# Radio.net
KiCad netlist of a schematic drawn in Altium Designer
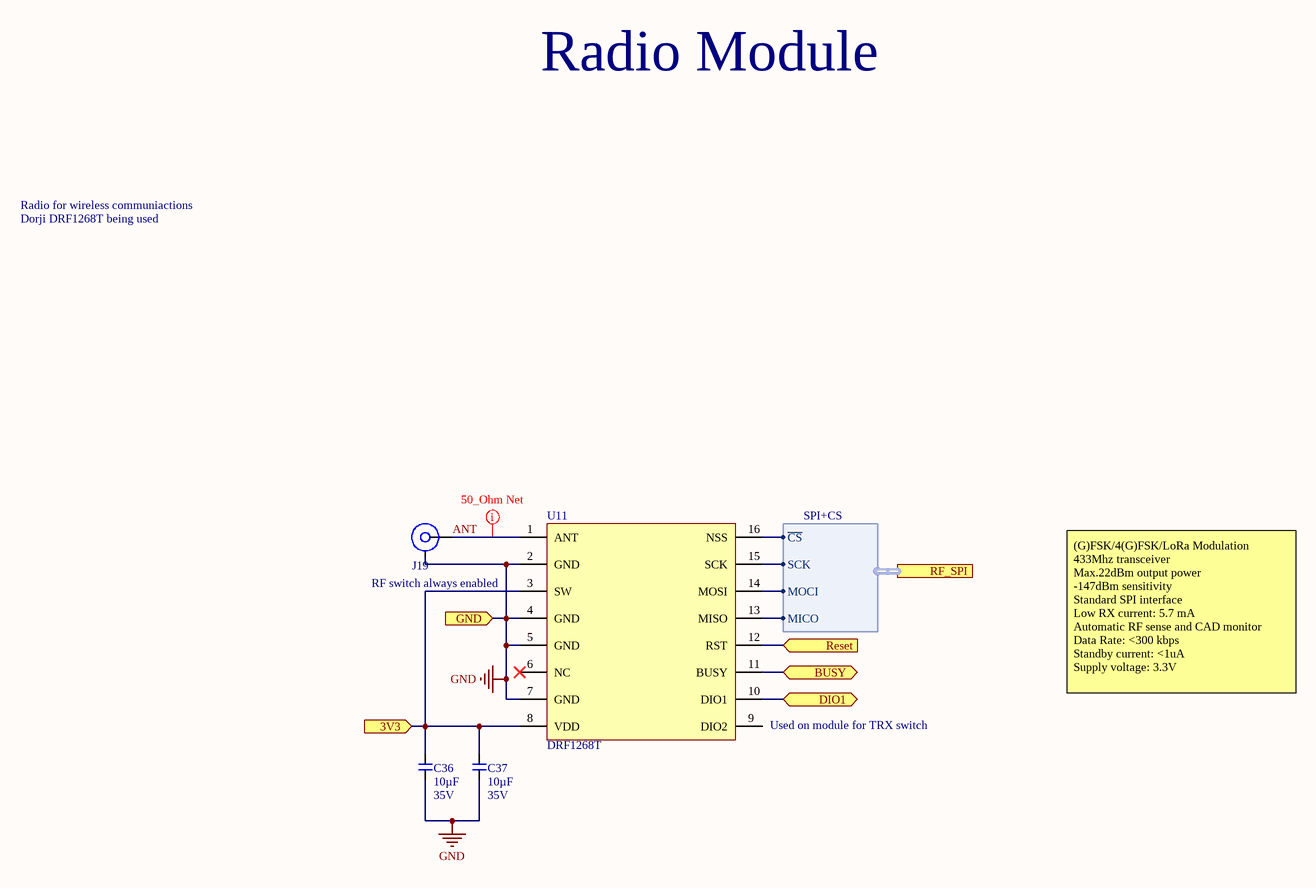
[diagram p0: Radio.SchDoc]

(export (version "E")
  (design (tool "Eeschema 10.0.6"))
  (components
    (comp (ref "C36")
      (value "490-13248-1-ND")
      (footprint "C0603")
      (description "CAP CER 10UF 35V X5R 0603 20%")
      (fields
        (field (name "CAPACITANCE (SHORTHAND)") "10µF")
        (field (name "RATED VOLTAGE") "35V")
        (field (name "MANUFACTURER") "Murata Electronics North America")
      )
      (libsource (lib "Stanford Student Space Initiative") (part "__template_cap"))
    )
    (comp (ref "C37")
      (value "490-13248-1-ND")
      (footprint "C0603")
      (description "CAP CER 10UF 35V X5R 0603 20%")
      (fields
        (field (name "CAPACITANCE (SHORTHAND)") "10µF")
        (field (name "RATED VOLTAGE") "35V")
        (field (name "MANUFACTURER") "Murata Electronics North America")
      )
      (libsource (lib "Stanford Student Space Initiative") (part "__template_cap"))
    )
    (comp (ref "J19")
      (value "SMA_SAMTEC_TH_RA")
      (footprint "SMA_SAMTEC_SMA-J-P-X-RA-TH1")
      (libsource (lib "Stanford Student Space Initiative") (part "SMA_SAMTEC_TH_RA"))
    )
    (comp (ref "U11")
      (value "DRF1268T")
      (footprint "DRF1268T")
      (description "Dorji DRF1268T LoRa Module with SX1262 IC and TCXO")
      (libsource (lib "Stanford Student Space Initiative") (part "DRF1268T"))
    )
  )
  (nets
    (net (code "2") (name "/3V3") (class "Default")
      (node (ref "C36") (pin "1") (pintype "passive"))
      (node (ref "C37") (pin "1") (pintype "passive"))
      (node (ref "U11") (pin "3") (pinfunction "SW_3") (pintype "passive"))
      (node (ref "U11") (pin "8") (pinfunction "VDD_8") (pintype "passive"))
    )
    (net (code "3") (name "/ANT") (class "Default")
      (node (ref "J19") (pin "SIG") (pinfunction "SIG_SIG") (pintype "passive"))
      (node (ref "U11") (pin "1") (pinfunction "ANT_1") (pintype "passive"))
    )
    (net (code "4") (name "/BUSY") (class "Default")
      (node (ref "U11") (pin "11") (pinfunction "BUSY_11") (pintype "passive"))
    )
    (net (code "5") (name "/DIO1") (class "Default")
      (node (ref "U11") (pin "10") (pinfunction "DIO1_10") (pintype "passive"))
    )
    (net (code "6") (name "/MICO") (class "Default")
      (node (ref "U11") (pin "13") (pinfunction "MISO_13") (pintype "passive"))
    )
    (net (code "7") (name "/MOCI") (class "Default")
      (node (ref "U11") (pin "14") (pinfunction "MOSI_14") (pintype "passive"))
    )
    (net (code "8") (name "/Reset") (class "Default")
      (node (ref "U11") (pin "12") (pinfunction "RST_12") (pintype "passive"))
    )
    (net (code "9") (name "/SCK") (class "Default")
      (node (ref "U11") (pin "15") (pinfunction "SCK_15") (pintype "passive"))
    )
    (net (code "11") (name "/~{CS}") (class "Default")
      (node (ref "U11") (pin "16") (pinfunction "NSS_16") (pintype "passive"))
    )
    (net (code "12") (name "GND") (class "Default")
      (node (ref "C36") (pin "2") (pintype "passive"))
      (node (ref "C37") (pin "2") (pintype "passive"))
      (node (ref "J19") (pin "GND") (pinfunction "GND_GND") (pintype "passive"))
      (node (ref "U11") (pin "2") (pinfunction "GND_2") (pintype "passive"))
      (node (ref "U11") (pin "4") (pinfunction "GND_4") (pintype "passive"))
      (node (ref "U11") (pin "5") (pinfunction "GND_5") (pintype "passive"))
      (node (ref "U11") (pin "7") (pinfunction "GND_7") (pintype "passive"))
    )
    (net (code "13") (name "unconnected-(U11-DIO2-Pad9)") (class "Default")
      (node (ref "U11") (pin "9") (pinfunction "DIO2_9") (pintype "passive"))
    )
    (net (code "14") (name "unconnected-(U11-NC-Pad6)") (class "Default")
      (node (ref "U11") (pin "6") (pinfunction "NC_6") (pintype "passive+no_connect"))
    )
  )
)
